# LED_Driver.net
KiCad netlist of a schematic drawn in EAGLE
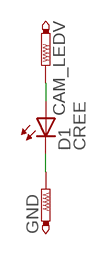
[diagram p0: schematic, sheet 1]

(export (version "E")
  (design (tool "Eeschema 10.0.6"))
  (components
    (comp (ref "CAM_LEDV")
      (value "PTR1PAD1-20")
      (footprint "eagle-import:P1-20")
      (libsource (lib "eagle-import") (part "PTR1PAD1-20"))
    )
    (comp (ref "D1")
      (value "CREE")
      (footprint "eagle-import:CREE-XLAMP-XM-L")
      (libsource (lib "eagle-import") (part "CREE"))
    )
    (comp (ref "GND")
      (value "PTR1PAD1-20")
      (footprint "eagle-import:P1-20")
      (libsource (lib "eagle-import") (part "PTR1PAD1-20"))
    )
  )
  (nets
    (net (code "1") (name "Net-(CAM_LEDV-PadTP)") (class "Default")
      (node (ref "CAM_LEDV") (pin "TP") (pinfunction "TP_TP") (pintype "input"))
      (node (ref "D1") (pin "A") (pinfunction "A_A") (pintype "input"))
      (node (ref "D1") (pin "A@1") (pinfunction "A_A@1") (pintype "input"))
    )
    (net (code "2") (name "Net-(D1-C-PadC1)") (class "Default")
      (node (ref "D1") (pin "C") (pinfunction "C_C") (pintype "output"))
      (node (ref "D1") (pin "C1") (pinfunction "C_C1") (pintype "output"))
      (node (ref "D1") (pin "C@1") (pinfunction "C_C@1") (pintype "output"))
      (node (ref "GND") (pin "TP") (pinfunction "TP_TP") (pintype "input"))
    )
  )
)
